# 1_POWER.net
KiCad netlist of a schematic drawn in Altium Designer
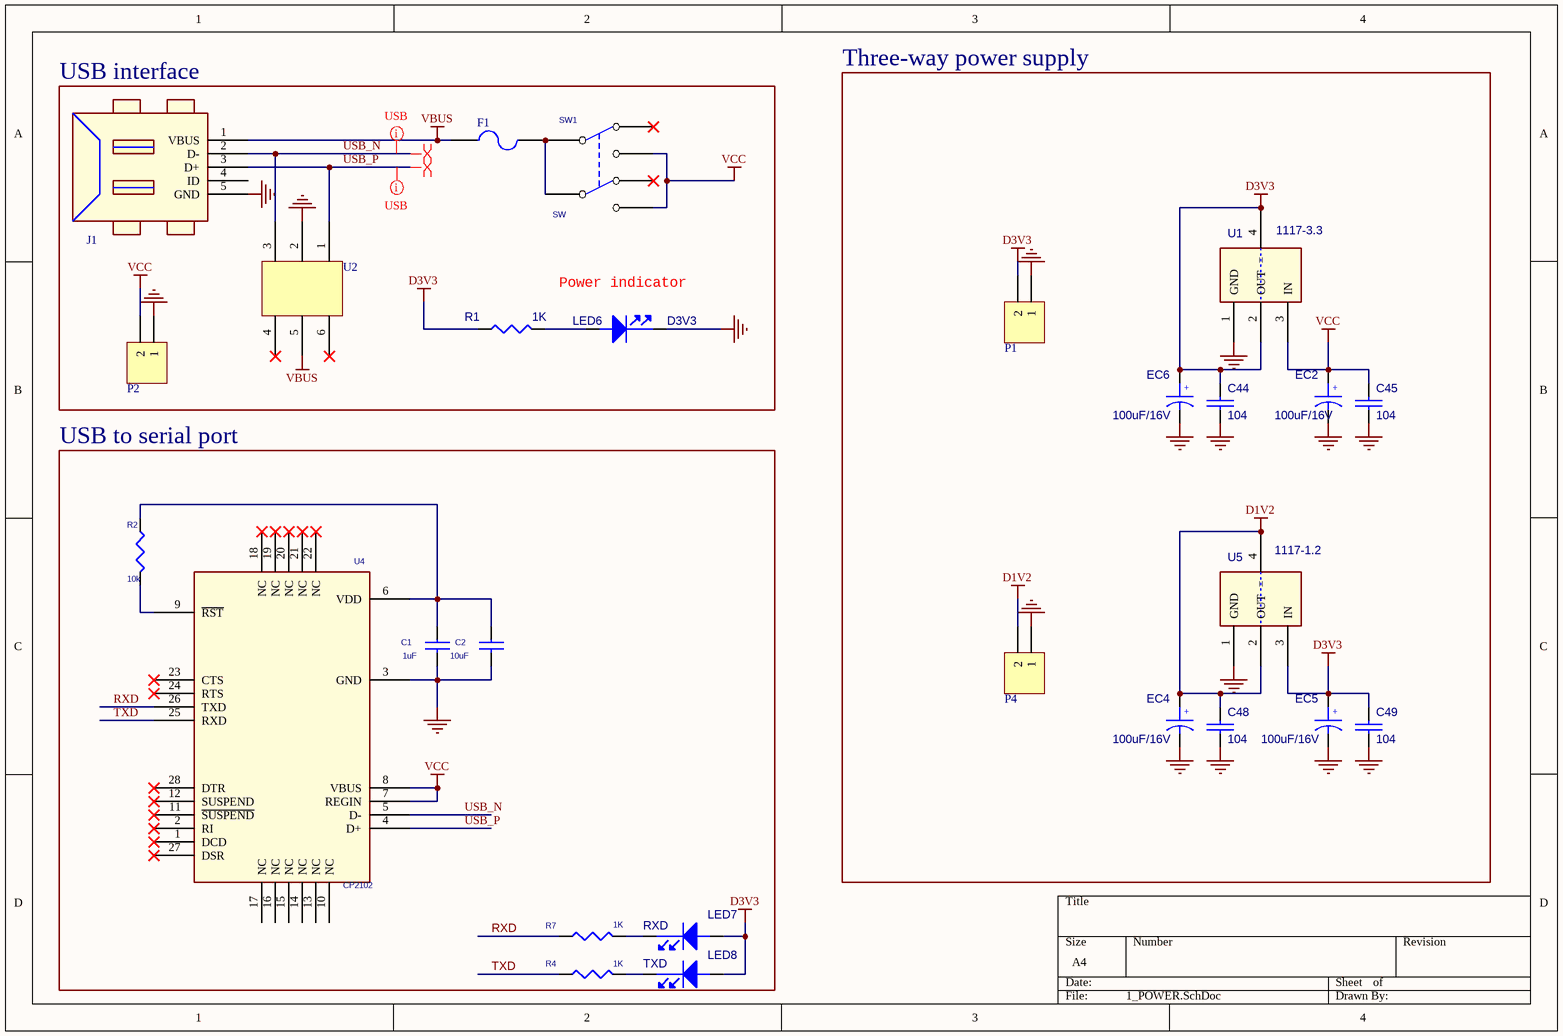
[diagram p0: 1_POWER.SchDoc]

(export (version "E")
  (design (tool "Eeschema 10.0.6"))
  (components
    (comp (ref "C1") (value "1uF") (libsource (lib "*") (part "CAP NP_Dup2")))
    (comp (ref "C2") (value "10uF") (libsource (lib "*") (part "CAP NP_Dup2")))
    (comp (ref "C44") (value "104") (libsource (lib "*") (part "C_Dup4")))
    (comp (ref "C45") (value "104") (libsource (lib "*") (part "C_Dup4")))
    (comp (ref "C48") (value "104") (libsource (lib "*") (part "C_Dup4")))
    (comp (ref "C49") (value "104") (libsource (lib "*") (part "C_Dup4")))
    (comp (ref "EC2") (value "100uF/16V") (libsource (lib "*") (part "EC")))
    (comp (ref "EC4") (value "100uF/16V") (libsource (lib "*") (part "EC")))
    (comp (ref "EC5") (value "100uF/16V") (libsource (lib "*") (part "EC")))
    (comp (ref "EC6") (value "100uF/16V") (libsource (lib "*") (part "EC")))
    (comp (ref "F1")
      (value "~")
      (footprint "AX309:1206")
      (description "Fuse")
      (fields (field (name "PUBLISHER") "Altium Limited"))
      (libsource (lib "Xilinx Spartan-6") (part "Fuse 2"))
    )
    (comp (ref "J1") (value "EC2") (footprint "MINIUSBB") (libsource (lib "*") (part "MiniUSBB")))
    (comp (ref "LED6") (value "D3V3") (footprint "LEDSO") (libsource (lib "*") (part "LED_Dup1")))
    (comp (ref "LED7") (value "RXD") (footprint "LEDSO") (libsource (lib "*") (part "LED")))
    (comp (ref "LED8") (value "TXD") (footprint "LEDSO") (libsource (lib "*") (part "LED")))
    (comp (ref "P1")
      (value "3.3V")
      (footprint "HDR1X2")
      (description "Header, 2-Pin")
      (fields (field (name "PUBLISHER") "Altium Limited"))
      (libsource (lib "Miscellaneous Connectors") (part "Header 2"))
    )
    (comp (ref "P2")
      (value "5V")
      (footprint "HDR1X2")
      (description "Header, 2-Pin")
      (fields (field (name "PUBLISHER") "Altium Limited"))
      (libsource (lib "Miscellaneous Connectors") (part "Header 2"))
    )
    (comp (ref "P4")
      (value "1.2V")
      (footprint "HDR1X2")
      (description "Header, 2-Pin")
      (fields (field (name "PUBLISHER") "Altium Limited"))
      (libsource (lib "Miscellaneous Connectors") (part "Header 2"))
    )
    (comp (ref "R1") (value "1K") (footprint "0603") (libsource (lib "*") (part "R")))
    (comp (ref "R2") (value "10k") (libsource (lib "*") (part "RESISTOR")))
    (comp (ref "R4") (value "1K") (footprint "0603") (libsource (lib "*") (part "R_Dup3")))
    (comp (ref "R7") (value "1K") (footprint "0603") (libsource (lib "*") (part "R_Dup3")))
    (comp (ref "SW1") (value "SW") (libsource (lib "*") (part "SW KEY-DPDT")))
    (comp (ref "U1") (value "1117-3.3") (footprint "SOT223") (libsource (lib "*") (part "1117-3.3")))
    (comp (ref "U2")
      (value "~")
      (footprint "RezMir:SOT23-6")
      (libsource (lib "Xilinx Spartan-6") (part "SRV05-4"))
    )
    (comp (ref "U4") (value "CP2102") (libsource (lib "*") (part "CP2102_0")))
    (comp (ref "U5") (value "1117-1.2") (footprint "SOT223") (libsource (lib "*") (part "1117-3.3")))
  )
  (nets
    (net (code "1") (name "/RXD") (class "Default")
      (node (ref "R7") (pin "1") (pinfunction "1_1") (pintype "passive"))
      (node (ref "U4") (pin "26") (pinfunction "TXD_26") (pintype "passive"))
    )
    (net (code "2") (name "/TXD") (class "Default")
      (node (ref "R4") (pin "1") (pinfunction "1_1") (pintype "passive"))
      (node (ref "U4") (pin "25") (pinfunction "RXD_25") (pintype "passive"))
    )
    (net (code "3") (name "/USB_N") (class "Default")
      (node (ref "J1") (pin "2") (pinfunction "D-_2") (pintype "passive"))
      (node (ref "U2") (pin "3") (pinfunction "3_3") (pintype "passive"))
      (node (ref "U4") (pin "5") (pinfunction "D-_5") (pintype "passive"))
    )
    (net (code "4") (name "/USB_P") (class "Default")
      (node (ref "J1") (pin "3") (pinfunction "D+_3") (pintype "passive"))
      (node (ref "U2") (pin "1") (pinfunction "1_1") (pintype "passive"))
      (node (ref "U4") (pin "4") (pinfunction "D+_4") (pintype "passive"))
    )
    (net (code "5") (name "D1V2") (class "Default")
      (node (ref "C48") (pin "1") (pinfunction "1_1") (pintype "passive"))
      (node (ref "EC4") (pin "1") (pinfunction "1_1") (pintype "passive"))
      (node (ref "P4") (pin "2") (pinfunction "2_2") (pintype "passive"))
      (node (ref "U5") (pin "2") (pinfunction "OUT_2") (pintype "passive"))
      (node (ref "U5") (pin "4") (pinfunction "=_4") (pintype "passive"))
    )
    (net (code "6") (name "D3V3") (class "Default")
      (node (ref "C44") (pin "1") (pinfunction "1_1") (pintype "passive"))
      (node (ref "C49") (pin "1") (pinfunction "1_1") (pintype "passive"))
      (node (ref "EC5") (pin "1") (pinfunction "1_1") (pintype "passive"))
      (node (ref "EC6") (pin "1") (pinfunction "1_1") (pintype "passive"))
      (node (ref "LED7") (pin "1") (pinfunction "ANODE_1") (pintype "passive"))
      (node (ref "LED8") (pin "1") (pinfunction "ANODE_1") (pintype "passive"))
      (node (ref "P1") (pin "2") (pinfunction "2_2") (pintype "passive"))
      (node (ref "R1") (pin "1") (pinfunction "1_1") (pintype "passive"))
      (node (ref "U1") (pin "2") (pinfunction "OUT_2") (pintype "passive"))
      (node (ref "U1") (pin "4") (pinfunction "=_4") (pintype "passive"))
      (node (ref "U5") (pin "3") (pinfunction "IN_3") (pintype "passive"))
    )
    (net (code "7") (name "GND") (class "Default")
      (node (ref "C1") (pin "2") (pinfunction "2_2") (pintype "passive"))
      (node (ref "C2") (pin "2") (pinfunction "2_2") (pintype "passive"))
      (node (ref "C44") (pin "2") (pinfunction "2_2") (pintype "passive"))
      (node (ref "C45") (pin "2") (pinfunction "2_2") (pintype "passive"))
      (node (ref "C48") (pin "2") (pinfunction "2_2") (pintype "passive"))
      (node (ref "C49") (pin "2") (pinfunction "2_2") (pintype "passive"))
      (node (ref "EC2") (pin "2") (pinfunction "2_2") (pintype "passive"))
      (node (ref "EC4") (pin "2") (pinfunction "2_2") (pintype "passive"))
      (node (ref "EC5") (pin "2") (pinfunction "2_2") (pintype "passive"))
      (node (ref "EC6") (pin "2") (pinfunction "2_2") (pintype "passive"))
      (node (ref "J1") (pin "5") (pinfunction "GND_5") (pintype "passive"))
      (node (ref "LED6") (pin "2") (pinfunction "CATHODE_2") (pintype "passive"))
      (node (ref "P1") (pin "1") (pinfunction "1_1") (pintype "passive"))
      (node (ref "P2") (pin "1") (pinfunction "1_1") (pintype "passive"))
      (node (ref "P4") (pin "1") (pinfunction "1_1") (pintype "passive"))
      (node (ref "U1") (pin "1") (pinfunction "GND_1") (pintype "passive"))
      (node (ref "U2") (pin "2") (pinfunction "2_2") (pintype "passive"))
      (node (ref "U4") (pin "3") (pinfunction "GND_3") (pintype "power_in"))
      (node (ref "U5") (pin "1") (pinfunction "GND_1") (pintype "passive"))
    )
    (net (code "8") (name "Net-(LED6-ANODE)") (class "Default")
      (node (ref "LED6") (pin "1") (pinfunction "ANODE_1") (pintype "passive"))
      (node (ref "R1") (pin "2") (pinfunction "2_2") (pintype "passive"))
    )
    (net (code "9") (name "Net-(LED7-CATHODE)") (class "Default")
      (node (ref "LED7") (pin "2") (pinfunction "CATHODE_2") (pintype "passive"))
      (node (ref "R7") (pin "2") (pinfunction "2_2") (pintype "passive"))
    )
    (net (code "10") (name "Net-(LED8-CATHODE)") (class "Default")
      (node (ref "LED8") (pin "2") (pinfunction "CATHODE_2") (pintype "passive"))
      (node (ref "R4") (pin "2") (pinfunction "2_2") (pintype "passive"))
    )
    (net (code "11") (name "Net-(SW1-COMMON1)") (class "Default")
      (node (ref "F1") (pin "2") (pinfunction "2_2") (pintype "passive"))
      (node (ref "SW1") (pin "2") (pinfunction "COMMON1_2") (pintype "passive"))
      (node (ref "SW1") (pin "5") (pinfunction "COMMON2_5") (pintype "passive"))
    )
    (net (code "12") (name "Net-(U4-VDD)") (class "Default")
      (node (ref "C1") (pin "1") (pinfunction "1_1") (pintype "passive"))
      (node (ref "C2") (pin "1") (pinfunction "1_1") (pintype "passive"))
      (node (ref "R2") (pin "2") (pinfunction "2_2") (pintype "passive"))
      (node (ref "U4") (pin "6") (pinfunction "VDD_6") (pintype "power_in"))
    )
    (net (code "13") (name "Net-(U4-~{RST})") (class "Default")
      (node (ref "R2") (pin "1") (pinfunction "1_1") (pintype "passive"))
      (node (ref "U4") (pin "9") (pinfunction "~{RST}_9") (pintype "passive"))
    )
    (net (code "14") (name "VBUS") (class "Default")
      (node (ref "F1") (pin "1") (pinfunction "1_1") (pintype "passive"))
      (node (ref "J1") (pin "1") (pinfunction "VBUS_1") (pintype "passive"))
      (node (ref "U2") (pin "5") (pinfunction "5_5") (pintype "passive"))
    )
    (net (code "15") (name "VCC") (class "Default")
      (node (ref "C45") (pin "1") (pinfunction "1_1") (pintype "passive"))
      (node (ref "EC2") (pin "1") (pinfunction "1_1") (pintype "passive"))
      (node (ref "P2") (pin "2") (pinfunction "2_2") (pintype "passive"))
      (node (ref "SW1") (pin "3") (pinfunction "NO1_3") (pintype "passive"))
      (node (ref "SW1") (pin "6") (pinfunction "NO2_6") (pintype "passive"))
      (node (ref "U1") (pin "3") (pinfunction "IN_3") (pintype "passive"))
      (node (ref "U4") (pin "7") (pinfunction "REGIN_7") (pintype "passive"))
      (node (ref "U4") (pin "8") (pinfunction "VBUS_8") (pintype "passive"))
    )
    (net (code "16") (name "unconnected-(J1-ID-Pad4)") (class "Default")
      (node (ref "J1") (pin "4") (pinfunction "ID_4") (pintype "passive"))
    )
    (net (code "17") (name "unconnected-(SW1-NC1-Pad1)") (class "Default")
      (node (ref "SW1") (pin "1") (pinfunction "NC1_1") (pintype "passive+no_connect"))
    )
    (net (code "18") (name "unconnected-(SW1-NC2-Pad4)") (class "Default")
      (node (ref "SW1") (pin "4") (pinfunction "NC2_4") (pintype "passive+no_connect"))
    )
    (net (code "19") (name "unconnected-(U2-Pad4)") (class "Default")
      (node (ref "U2") (pin "4") (pinfunction "4_4") (pintype "passive+no_connect"))
    )
    (net (code "20") (name "unconnected-(U2-Pad6)") (class "Default")
      (node (ref "U2") (pin "6") (pinfunction "6_6") (pintype "passive+no_connect"))
    )
    (net (code "21") (name "unconnected-(U4-CTS-Pad23)") (class "Default")
      (node (ref "U4") (pin "23") (pinfunction "CTS_23") (pintype "passive+no_connect"))
    )
    (net (code "22") (name "unconnected-(U4-DCD-Pad1)") (class "Default")
      (node (ref "U4") (pin "1") (pinfunction "DCD_1") (pintype "passive+no_connect"))
    )
    (net (code "23") (name "unconnected-(U4-DSR-Pad27)") (class "Default")
      (node (ref "U4") (pin "27") (pinfunction "DSR_27") (pintype "passive+no_connect"))
    )
    (net (code "24") (name "unconnected-(U4-DTR-Pad28)") (class "Default")
      (node (ref "U4") (pin "28") (pinfunction "DTR_28") (pintype "passive+no_connect"))
    )
    (net (code "25") (name "unconnected-(U4-NC-Pad10)") (class "Default")
      (node (ref "U4") (pin "10") (pinfunction "NC_10") (pintype "passive"))
    )
    (net (code "26") (name "unconnected-(U4-NC-Pad13)") (class "Default")
      (node (ref "U4") (pin "13") (pinfunction "NC_13") (pintype "passive"))
    )
    (net (code "27") (name "unconnected-(U4-NC-Pad14)") (class "Default")
      (node (ref "U4") (pin "14") (pinfunction "NC_14") (pintype "passive"))
    )
    (net (code "28") (name "unconnected-(U4-NC-Pad15)") (class "Default")
      (node (ref "U4") (pin "15") (pinfunction "NC_15") (pintype "passive"))
    )
    (net (code "29") (name "unconnected-(U4-NC-Pad16)") (class "Default")
      (node (ref "U4") (pin "16") (pinfunction "NC_16") (pintype "passive"))
    )
    (net (code "30") (name "unconnected-(U4-NC-Pad17)") (class "Default")
      (node (ref "U4") (pin "17") (pinfunction "NC_17") (pintype "passive"))
    )
    (net (code "31") (name "unconnected-(U4-NC-Pad18)") (class "Default")
      (node (ref "U4") (pin "18") (pinfunction "NC_18") (pintype "passive+no_connect"))
    )
    (net (code "32") (name "unconnected-(U4-NC-Pad19)") (class "Default")
      (node (ref "U4") (pin "19") (pinfunction "NC_19") (pintype "passive+no_connect"))
    )
    (net (code "33") (name "unconnected-(U4-NC-Pad20)") (class "Default")
      (node (ref "U4") (pin "20") (pinfunction "NC_20") (pintype "passive+no_connect"))
    )
    (net (code "34") (name "unconnected-(U4-NC-Pad21)") (class "Default")
      (node (ref "U4") (pin "21") (pinfunction "NC_21") (pintype "passive+no_connect"))
    )
    (net (code "35") (name "unconnected-(U4-NC-Pad22)") (class "Default")
      (node (ref "U4") (pin "22") (pinfunction "NC_22") (pintype "passive+no_connect"))
    )
    (net (code "36") (name "unconnected-(U4-RI-Pad2)") (class "Default")
      (node (ref "U4") (pin "2") (pinfunction "RI_2") (pintype "passive+no_connect"))
    )
    (net (code "37") (name "unconnected-(U4-RTS-Pad24)") (class "Default")
      (node (ref "U4") (pin "24") (pinfunction "RTS_24") (pintype "passive+no_connect"))
    )
    (net (code "38") (name "unconnected-(U4-SUSPEND-Pad12)") (class "Default")
      (node (ref "U4") (pin "12") (pinfunction "SUSPEND_12") (pintype "passive+no_connect"))
    )
    (net (code "39") (name "unconnected-(U4-~{SUSPEND}-Pad11)") (class "Default")
      (node (ref "U4") (pin "11") (pinfunction "~{SUSPEND}_11") (pintype "passive+no_connect"))
    )
  )
)
